# HVRescue_Shield_r212.net
KiCad netlist of a schematic drawn in EAGLE
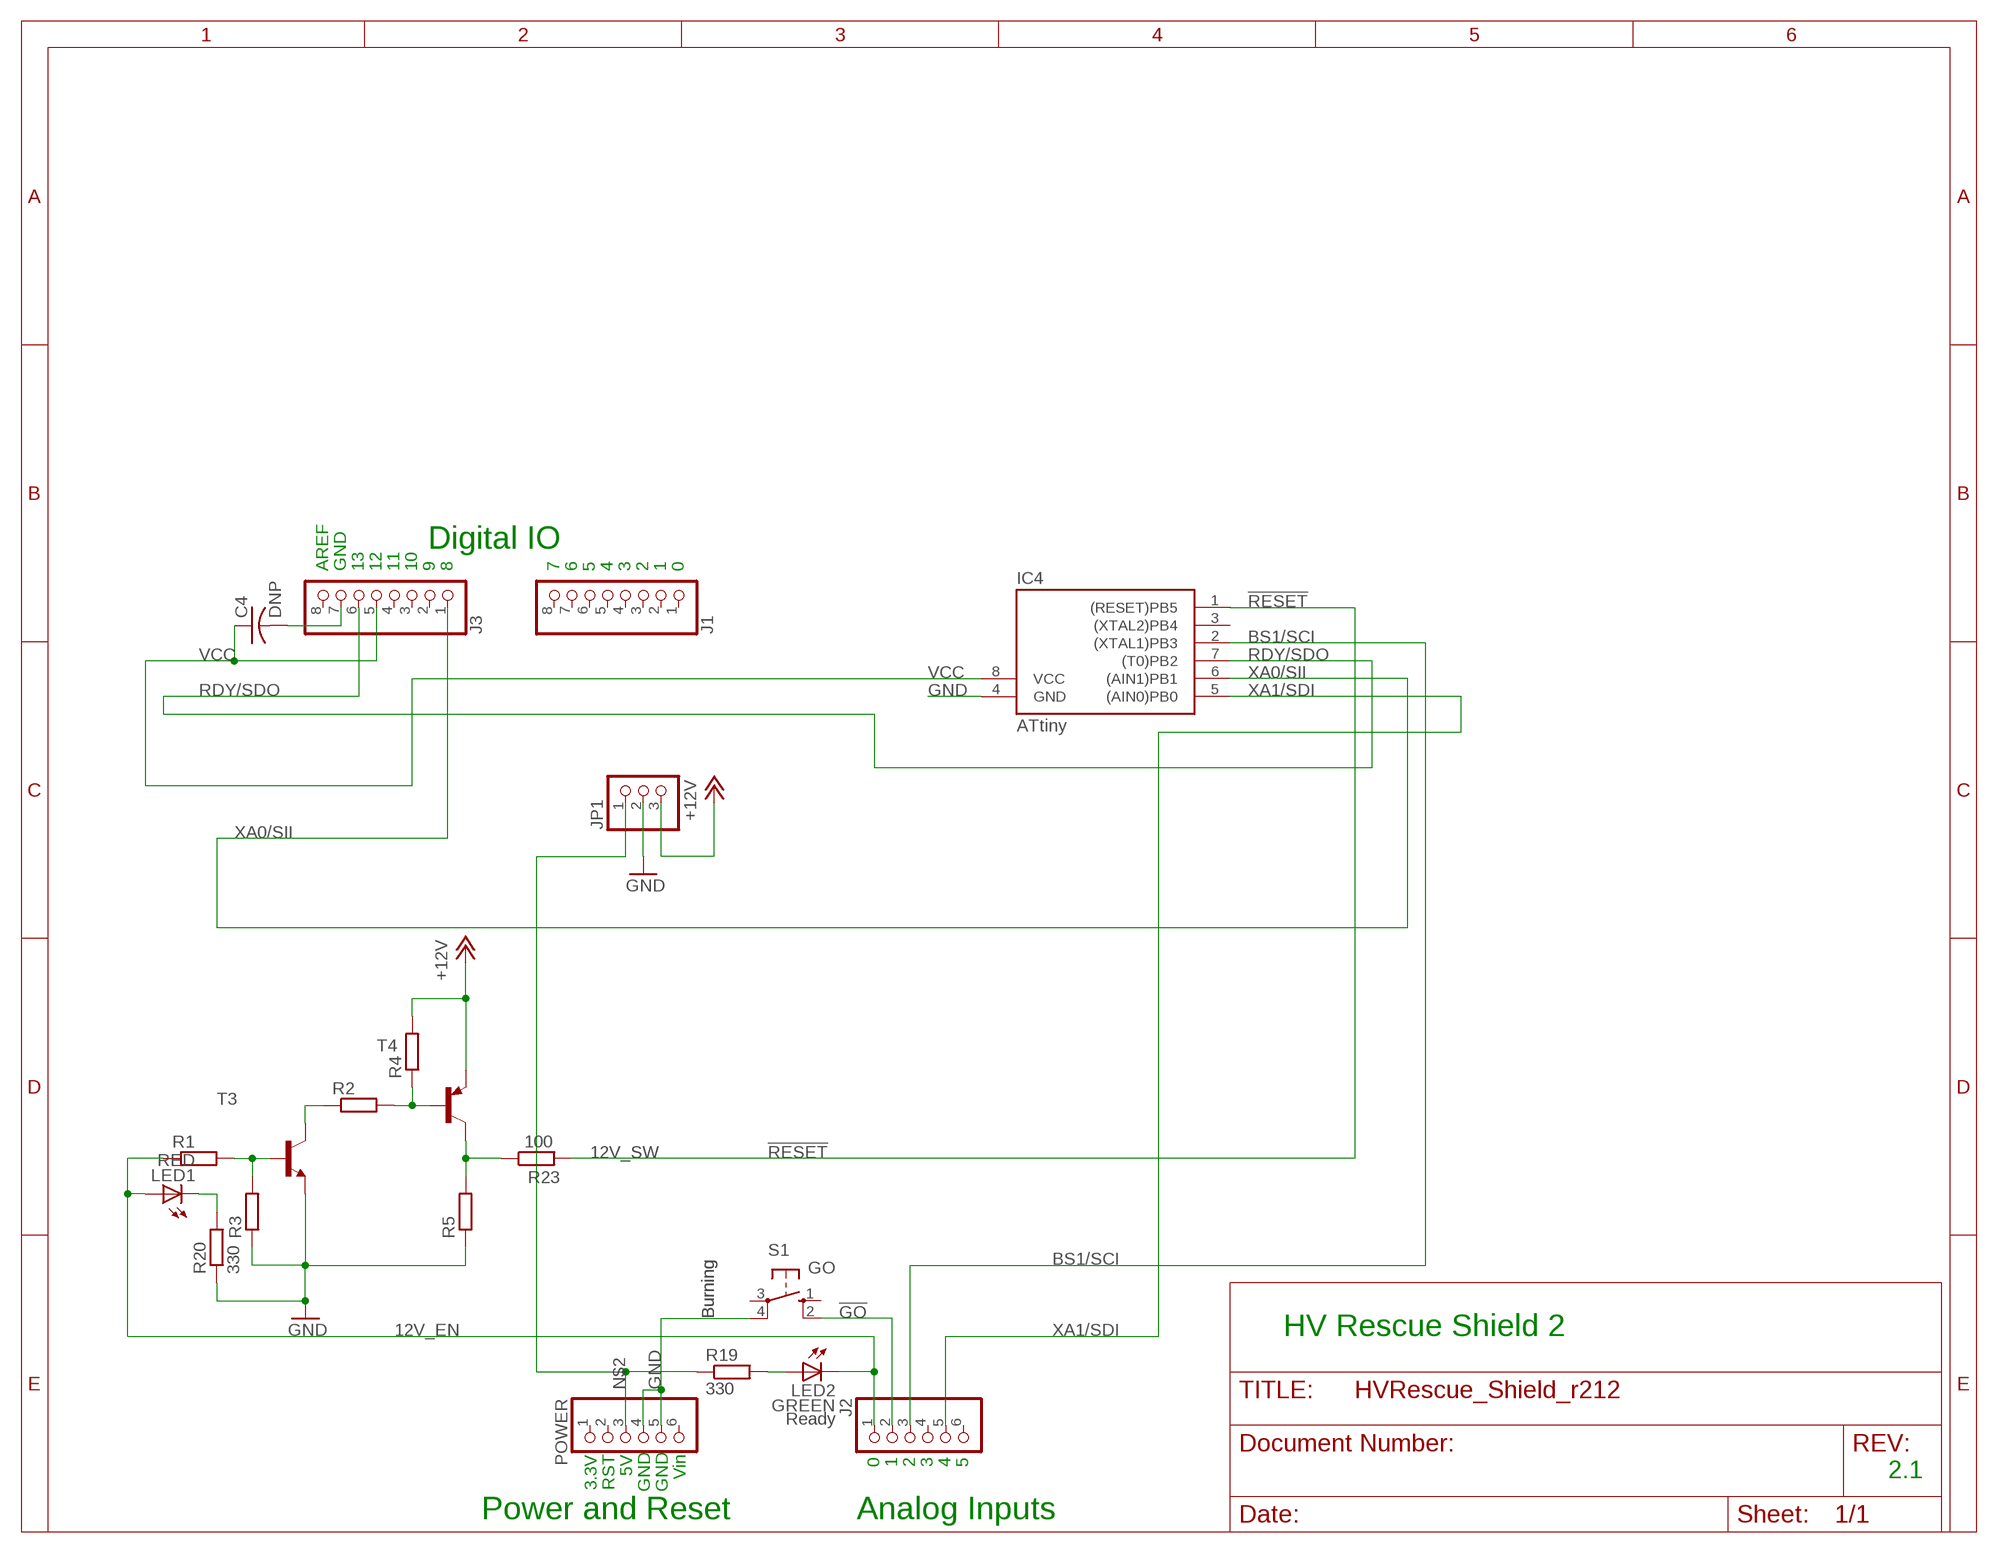
[diagram p0: schematic, sheet 1]

(export (version "E")
  (design (tool "Eeschema 10.0.6"))
  (components
    (comp (ref "C4")
      (value "DNP")
      (footprint "eagle-import:C025-025X050")
      (libsource (lib "eagle-import") (part "C-US025-025X050"))
    )
    (comp (ref "IC4")
      (value "ATtiny")
      (footprint "eagle-import:DIL08")
      (libsource (lib "eagle-import") (part "TINY10P"))
    )
    (comp (ref "J1")
      (value "PINHD-1X8")
      (footprint "eagle-import:1X08")
      (libsource (lib "eagle-import") (part "PINHD-1X8"))
    )
    (comp (ref "J2")
      (value "PINHD-1X6")
      (footprint "eagle-import:1X06")
      (libsource (lib "eagle-import") (part "PINHD-1X6"))
    )
    (comp (ref "J3")
      (value "PINHD-1X8")
      (footprint "eagle-import:1X08")
      (libsource (lib "eagle-import") (part "PINHD-1X8"))
    )
    (comp (ref "JP1")
      (value "PINHD-1X3")
      (footprint "eagle-import:1X03")
      (libsource (lib "eagle-import") (part "PINHD-1X3"))
    )
    (comp (ref "LED1")
      (value "RED")
      (footprint "eagle-import:LED3MM")
      (libsource (lib "eagle-import") (part "LED3MM"))
    )
    (comp (ref "LED2")
      (value "GREEN")
      (footprint "eagle-import:LED3MM")
      (libsource (lib "eagle-import") (part "LED3MM"))
    )
    (comp (ref "POWER")
      (value "PINHD-1X6")
      (footprint "eagle-import:1X06")
      (libsource (lib "eagle-import") (part "PINHD-1X6"))
    )
    (comp (ref "R1")
      (value "R-EU_0207/7")
      (footprint "eagle-import:0207_7")
      (libsource (lib "eagle-import") (part "R-EU_0207/7"))
    )
    (comp (ref "R2")
      (value "R-EU_0207/7")
      (footprint "eagle-import:0207_7")
      (libsource (lib "eagle-import") (part "R-EU_0207/7"))
    )
    (comp (ref "R3")
      (value "R-EU_0207/7")
      (footprint "eagle-import:0207_7")
      (libsource (lib "eagle-import") (part "R-EU_0207/7"))
    )
    (comp (ref "R4")
      (value "R-EU_0207/7")
      (footprint "eagle-import:0207_7")
      (libsource (lib "eagle-import") (part "R-EU_0207/7"))
    )
    (comp (ref "R5")
      (value "R-EU_0207/7")
      (footprint "eagle-import:0207_7")
      (libsource (lib "eagle-import") (part "R-EU_0207/7"))
    )
    (comp (ref "R19")
      (value "330")
      (footprint "eagle-import:0207_7")
      (libsource (lib "eagle-import") (part "R-EU_0207/7"))
    )
    (comp (ref "R20")
      (value "330")
      (footprint "eagle-import:0207_7")
      (libsource (lib "eagle-import") (part "R-EU_0207/7"))
    )
    (comp (ref "R23")
      (value "100")
      (footprint "eagle-import:0207_7")
      (libsource (lib "eagle-import") (part "R-EU_0207/7"))
    )
    (comp (ref "S1")
      (value "GO")
      (footprint "eagle-import:B3F-10XX")
      (fields (field (name "MPN") "B3F-1000"))
      (libsource (lib "eagle-import") (part "10-XX"))
    )
    (comp (ref "T3")
      (value "-NPN-TO92-ECB")
      (footprint "eagle-import:TO92-ECB")
      (libsource (lib "eagle-import") (part "-NPN-TO92-ECB"))
    )
    (comp (ref "T4")
      (value "-PNP-TO92-CEB")
      (footprint "eagle-import:TO92-CEB")
      (libsource (lib "eagle-import") (part "-PNP-TO92-CEB"))
    )
  )
  (nets
    (net (code "1") (name "+12V") (class "Default")
      (node (ref "JP1") (pin "3") (pinfunction "3_3") (pintype "passive"))
      (node (ref "R4") (pin "2") (pinfunction "2_2") (pintype "passive"))
      (node (ref "T4") (pin "E") (pinfunction "E_E") (pintype "passive"))
    )
    (net (code "2") (name "/12V_EN") (class "Default")
      (node (ref "J2") (pin "1") (pinfunction "1_1") (pintype "passive"))
      (node (ref "LED1") (pin "A") (pinfunction "A_A") (pintype "passive"))
      (node (ref "LED2") (pin "K") (pinfunction "C_K") (pintype "passive"))
      (node (ref "R1") (pin "1") (pinfunction "1_1") (pintype "passive"))
    )
    (net (code "3") (name "/12V_SW") (class "Default")
      (node (ref "R23") (pin "1") (pinfunction "1_1") (pintype "passive"))
      (node (ref "R5") (pin "2") (pinfunction "2_2") (pintype "passive"))
      (node (ref "T4") (pin "C") (pinfunction "C_C") (pintype "passive"))
    )
    (net (code "4") (name "/BS1{slash}SCI") (class "Default")
      (node (ref "IC4") (pin "2") (pinfunction "(XTAL1)PB3_2") (pintype "bidirectional"))
      (node (ref "J2") (pin "3") (pinfunction "3_3") (pintype "passive"))
    )
    (net (code "5") (name "/N$2") (class "Default")
      (node (ref "JP1") (pin "1") (pinfunction "1_1") (pintype "passive"))
      (node (ref "POWER") (pin "3") (pinfunction "3_3") (pintype "passive"))
      (node (ref "R19") (pin "1") (pinfunction "1_1") (pintype "passive"))
    )
    (net (code "6") (name "/RDY{slash}SDO") (class "Default")
      (node (ref "IC4") (pin "7") (pinfunction "(T0)PB2_7") (pintype "bidirectional"))
      (node (ref "J3") (pin "6") (pinfunction "6_6") (pintype "passive"))
    )
    (net (code "7") (name "/VCC") (class "Default")
      (node (ref "C4") (pin "1") (pinfunction "1_1") (pintype "passive"))
      (node (ref "IC4") (pin "8") (pinfunction "VCC_8") (pintype "power_in"))
      (node (ref "J3") (pin "5") (pinfunction "5_5") (pintype "passive"))
    )
    (net (code "8") (name "/XA0{slash}SII") (class "Default")
      (node (ref "IC4") (pin "6") (pinfunction "(AIN1)PB1_6") (pintype "bidirectional"))
      (node (ref "J3") (pin "1") (pinfunction "1_1") (pintype "passive"))
    )
    (net (code "9") (name "/XA1{slash}SDI") (class "Default")
      (node (ref "IC4") (pin "5") (pinfunction "(AIN0)PB0_5") (pintype "bidirectional"))
      (node (ref "J2") (pin "5") (pinfunction "5_5") (pintype "passive"))
    )
    (net (code "10") (name "/~{GO}") (class "Default")
      (node (ref "J2") (pin "2") (pinfunction "2_2") (pintype "passive"))
      (node (ref "S1") (pin "2") (pinfunction "S1_2") (pintype "passive"))
    )
    (net (code "11") (name "/~{RESET}") (class "Default")
      (node (ref "IC4") (pin "1") (pinfunction "(RESET)PB5_1") (pintype "bidirectional"))
      (node (ref "R23") (pin "2") (pinfunction "2_2") (pintype "passive"))
    )
    (net (code "12") (name "GND") (class "Default")
      (node (ref "IC4") (pin "4") (pinfunction "GND_4") (pintype "power_in"))
      (node (ref "JP1") (pin "2") (pinfunction "2_2") (pintype "passive"))
      (node (ref "POWER") (pin "4") (pinfunction "4_4") (pintype "passive"))
      (node (ref "POWER") (pin "5") (pinfunction "5_5") (pintype "passive"))
      (node (ref "R20") (pin "1") (pinfunction "1_1") (pintype "passive"))
      (node (ref "R3") (pin "1") (pinfunction "1_1") (pintype "passive"))
      (node (ref "R5") (pin "1") (pinfunction "1_1") (pintype "passive"))
      (node (ref "S1") (pin "4") (pinfunction "P1_4") (pintype "passive"))
      (node (ref "T3") (pin "E") (pinfunction "E_E") (pintype "passive"))
    )
    (net (code "13") (name "Net-(C4-Pad2)") (class "Default")
      (node (ref "C4") (pin "2") (pinfunction "2_2") (pintype "passive"))
      (node (ref "J3") (pin "7") (pinfunction "7_7") (pintype "passive"))
    )
    (net (code "14") (name "Net-(LED1-C)") (class "Default")
      (node (ref "LED1") (pin "K") (pinfunction "C_K") (pintype "passive"))
      (node (ref "R20") (pin "2") (pinfunction "2_2") (pintype "passive"))
    )
    (net (code "15") (name "Net-(LED2-PadA)") (class "Default")
      (node (ref "LED2") (pin "A") (pinfunction "A_A") (pintype "passive"))
      (node (ref "R19") (pin "2") (pinfunction "2_2") (pintype "passive"))
    )
    (net (code "16") (name "Net-(R1-Pad2)") (class "Default")
      (node (ref "R1") (pin "2") (pinfunction "2_2") (pintype "passive"))
      (node (ref "R3") (pin "2") (pinfunction "2_2") (pintype "passive"))
      (node (ref "T3") (pin "B") (pinfunction "B_B") (pintype "passive"))
    )
    (net (code "17") (name "Net-(R2-Pad1)") (class "Default")
      (node (ref "R2") (pin "1") (pinfunction "1_1") (pintype "passive"))
      (node (ref "T3") (pin "C") (pinfunction "C_C") (pintype "passive"))
    )
    (net (code "18") (name "Net-(R2-Pad2)") (class "Default")
      (node (ref "R2") (pin "2") (pinfunction "2_2") (pintype "passive"))
      (node (ref "R4") (pin "1") (pinfunction "1_1") (pintype "passive"))
      (node (ref "T4") (pin "B") (pinfunction "B_B") (pintype "passive"))
    )
    (net (code "19") (name "unconnected-(IC4-(XTAL2)PB4-Pad3)") (class "Default")
      (node (ref "IC4") (pin "3") (pinfunction "(XTAL2)PB4_3") (pintype "bidirectional"))
    )
    (net (code "20") (name "unconnected-(J1-Pad1)") (class "Default")
      (node (ref "J1") (pin "1") (pinfunction "1_1") (pintype "passive"))
    )
    (net (code "21") (name "unconnected-(J1-Pad2)") (class "Default")
      (node (ref "J1") (pin "2") (pinfunction "2_2") (pintype "passive"))
    )
    (net (code "22") (name "unconnected-(J1-Pad3)") (class "Default")
      (node (ref "J1") (pin "3") (pinfunction "3_3") (pintype "passive"))
    )
    (net (code "23") (name "unconnected-(J1-Pad4)") (class "Default")
      (node (ref "J1") (pin "4") (pinfunction "4_4") (pintype "passive"))
    )
    (net (code "24") (name "unconnected-(J1-Pad5)") (class "Default")
      (node (ref "J1") (pin "5") (pinfunction "5_5") (pintype "passive"))
    )
    (net (code "25") (name "unconnected-(J1-Pad6)") (class "Default")
      (node (ref "J1") (pin "6") (pinfunction "6_6") (pintype "passive"))
    )
    (net (code "26") (name "unconnected-(J1-Pad7)") (class "Default")
      (node (ref "J1") (pin "7") (pinfunction "7_7") (pintype "passive"))
    )
    (net (code "27") (name "unconnected-(J1-Pad8)") (class "Default")
      (node (ref "J1") (pin "8") (pinfunction "8_8") (pintype "passive"))
    )
    (net (code "28") (name "unconnected-(J2-Pad4)") (class "Default")
      (node (ref "J2") (pin "4") (pinfunction "4_4") (pintype "passive"))
    )
    (net (code "29") (name "unconnected-(J2-Pad6)") (class "Default")
      (node (ref "J2") (pin "6") (pinfunction "6_6") (pintype "passive"))
    )
    (net (code "30") (name "unconnected-(J3-Pad2)") (class "Default")
      (node (ref "J3") (pin "2") (pinfunction "2_2") (pintype "passive"))
    )
    (net (code "31") (name "unconnected-(J3-Pad3)") (class "Default")
      (node (ref "J3") (pin "3") (pinfunction "3_3") (pintype "passive"))
    )
    (net (code "32") (name "unconnected-(J3-Pad4)") (class "Default")
      (node (ref "J3") (pin "4") (pinfunction "4_4") (pintype "passive"))
    )
    (net (code "33") (name "unconnected-(J3-Pad8)") (class "Default")
      (node (ref "J3") (pin "8") (pinfunction "8_8") (pintype "passive"))
    )
    (net (code "34") (name "unconnected-(POWER-Pad1)") (class "Default")
      (node (ref "POWER") (pin "1") (pinfunction "1_1") (pintype "passive"))
    )
    (net (code "35") (name "unconnected-(POWER-Pad2)") (class "Default")
      (node (ref "POWER") (pin "2") (pinfunction "2_2") (pintype "passive"))
    )
    (net (code "36") (name "unconnected-(POWER-Pad6)") (class "Default")
      (node (ref "POWER") (pin "6") (pinfunction "6_6") (pintype "passive"))
    )
    (net (code "37") (name "unconnected-(S1-P-Pad3)") (class "Default")
      (node (ref "S1") (pin "3") (pinfunction "P_3") (pintype "passive"))
    )
    (net (code "38") (name "unconnected-(S1-S-Pad1)") (class "Default")
      (node (ref "S1") (pin "1") (pinfunction "S_1") (pintype "passive"))
    )
  )
)
